# nodo_AS.net
KiCad netlist of a schematic drawn in EAGLE
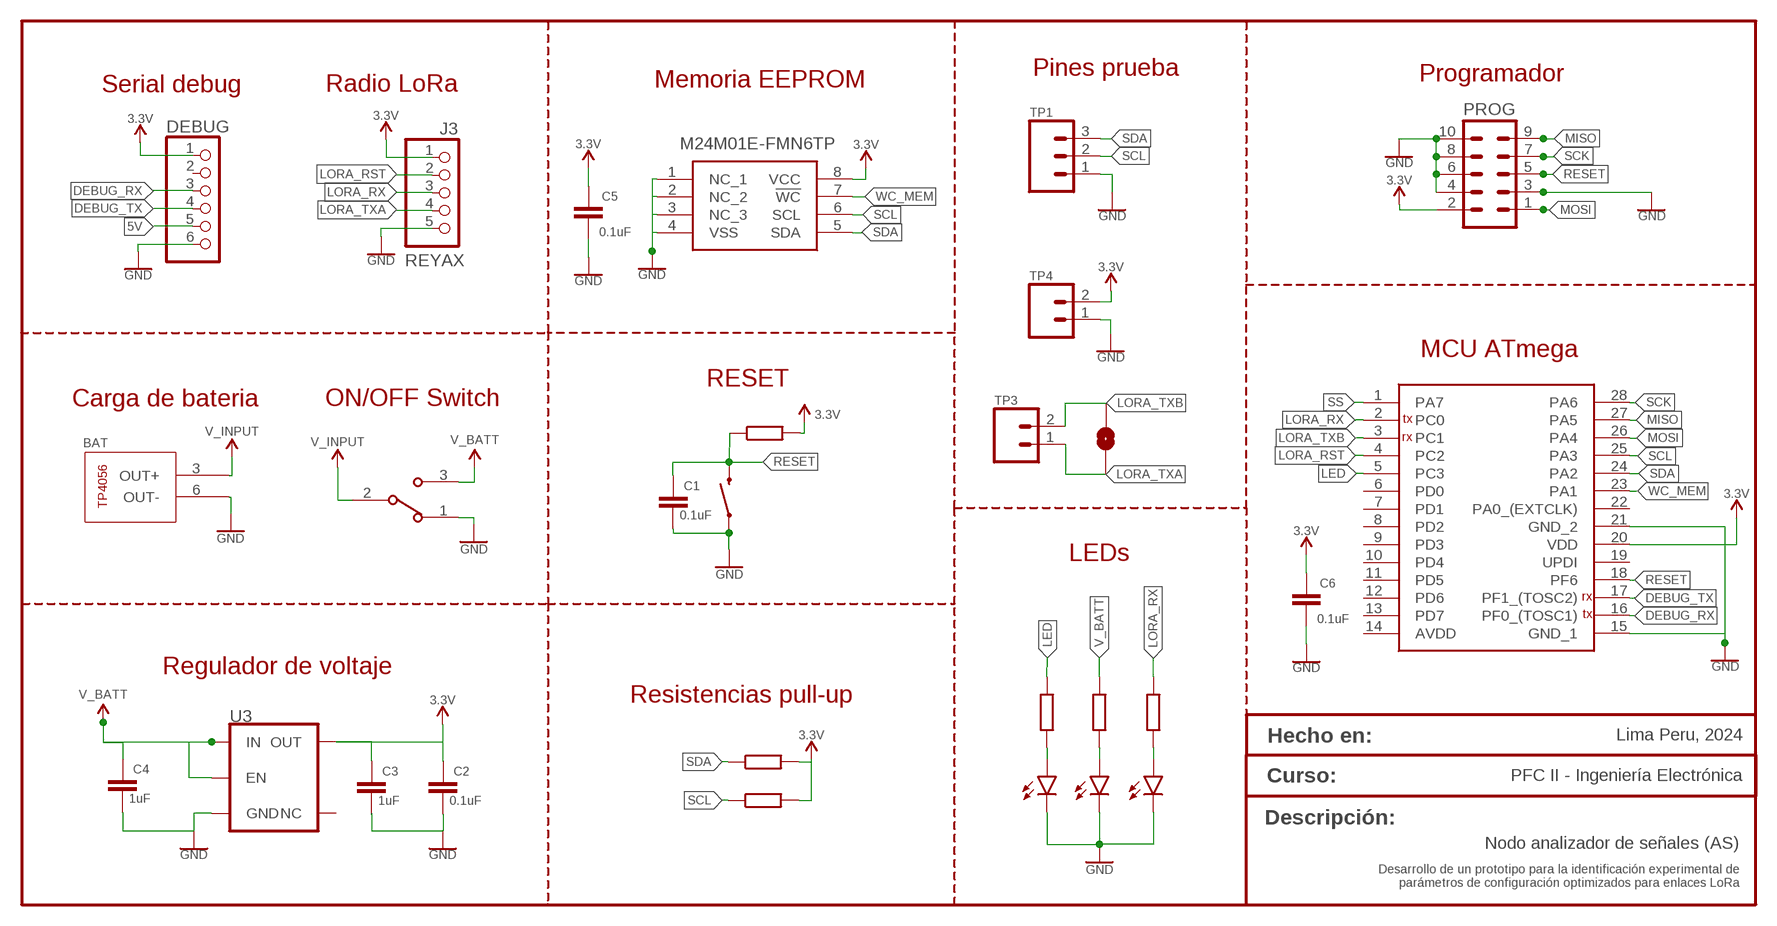
[diagram p0: schematic, sheet 1]

(export (version "E")
  (design (tool "Eeschema 10.0.6"))
  (components
    (comp (ref "BAT")
      (value "TP4056MODULE")
      (footprint "eagle-import:TP4056MODULE")
      (libsource (lib "eagle-import") (part "TP4056MODULE"))
    )
    (comp (ref "C1")
      (value "0.1uF")
      (footprint "eagle-import:C0603K")
      (libsource (lib "eagle-import") (part "C-EUC0603K"))
    )
    (comp (ref "C2")
      (value "0.1uF")
      (footprint "eagle-import:C0603K")
      (libsource (lib "eagle-import") (part "C-EUC0603K"))
    )
    (comp (ref "C3")
      (value "1uF")
      (footprint "eagle-import:C0603K")
      (libsource (lib "eagle-import") (part "C-EUC0603K"))
    )
    (comp (ref "C4")
      (value "1uF")
      (footprint "eagle-import:C0603K")
      (libsource (lib "eagle-import") (part "C-EUC0603K"))
    )
    (comp (ref "C5")
      (value "0.1uF")
      (footprint "eagle-import:0603")
      (libsource (lib "eagle-import") (part "0.1UF-0603-25V-(+80/-20%)"))
    )
    (comp (ref "C6")
      (value "0.1uF")
      (footprint "eagle-import:0603")
      (libsource (lib "eagle-import") (part "0.1UF-0603-25V-(+80/-20%)"))
    )
    (comp (ref "DEBUG")
      (value "PINHD-1X6")
      (footprint "eagle-import:1X06")
      (libsource (lib "eagle-import") (part "PINHD-1X6"))
    )
    (comp (ref "IC1")
      (value "ATMEGA3208-XU")
      (footprint "eagle-import:SOP65P780X200-28N")
      (fields (field (name "MOUSER_PART_NUMBER") "556-ATMEGA3208-XU"))
      (libsource (lib "eagle-import") (part "ATMEGA3208-XU"))
    )
    (comp (ref "IC2")
      (value "M24M01E-FMN6TP")
      (footprint "eagle-import:SOIC127P600X175-8N")
      (fields (field (name "MOUSER_PART_NUMBER") "511-M24M01E-FMN6TP"))
      (libsource (lib "eagle-import") (part "M24M01E-FMN6TP"))
    )
    (comp (ref "J3")
      (value "REYAX")
      (footprint "eagle-import:1X05")
      (libsource (lib "eagle-import") (part "PINHD-1X5"))
    )
    (comp (ref "JP1")
      (value "JUMPER-SMT_2_NO_NO-SILK_ROUND")
      (footprint "eagle-import:SMT-JUMPER_2_NO_NO-SILK_ROUND")
      (libsource (lib "eagle-import") (part "JUMPER-SMT_2_NO_NO-SILK_ROUND"))
    )
    (comp (ref "L_ON")
      (value "LED_3MM")
      (footprint "eagle-import:LEDRD254W50D405H1055")
      (libsource (lib "eagle-import") (part "LED_3MM"))
    )
    (comp (ref "L_ON1")
      (value "LED_3MM")
      (footprint "eagle-import:LEDRD254W50D405H1055")
      (libsource (lib "eagle-import") (part "LED_3MM"))
    )
    (comp (ref "L_ON2")
      (value "LED_3MM")
      (footprint "eagle-import:LEDRD254W50D405H1055")
      (libsource (lib "eagle-import") (part "LED_3MM"))
    )
    (comp (ref "PROG")
      (value "ML10-3M")
      (footprint "eagle-import:3M_10")
      (libsource (lib "eagle-import") (part "ML10-3M"))
    )
    (comp (ref "P_RESET")
      (value "MOMENTARY-SWITCH-SPST-PTH-6.0MM")
      (footprint "eagle-import:TACTILE_SWITCH_PTH_6.0MM")
      (libsource (lib "eagle-import") (part "MOMENTARY-SWITCH-SPST-PTH-6.0MM"))
    )
    (comp (ref "R1")
      (value "68")
      (footprint "eagle-import:0207_10")
      (libsource (lib "eagle-import") (part "R-EU_0207/10"))
    )
    (comp (ref "R2")
      (value "68")
      (footprint "eagle-import:0207_10")
      (libsource (lib "eagle-import") (part "R-EU_0207/10"))
    )
    (comp (ref "R3")
      (value "68")
      (footprint "eagle-import:0207_10")
      (libsource (lib "eagle-import") (part "R-EU_0207/10"))
    )
    (comp (ref "R4")
      (value "10k")
      (footprint "eagle-import:0207_10")
      (libsource (lib "eagle-import") (part "R-EU_0207/10"))
    )
    (comp (ref "R6")
      (value "1k")
      (footprint "eagle-import:0207_10")
      (libsource (lib "eagle-import") (part "R-EU_0207/10"))
    )
    (comp (ref "R7")
      (value "1k")
      (footprint "eagle-import:0207_10")
      (libsource (lib "eagle-import") (part "R-EU_0207/10"))
    )
    (comp (ref "SW1")
      (value "EG1213")
      (footprint "eagle-import:SW_EG1213")
      (fields (field (name "MF") "E-Switch"))
      (libsource (lib "eagle-import") (part "EG1213"))
    )
    (comp (ref "TP1")
      (value "CONN_03")
      (footprint "eagle-import:1X03")
      (libsource (lib "eagle-import") (part "CONN_03"))
    )
    (comp (ref "TP3")
      (value "CONN_02")
      (footprint "eagle-import:1X02")
      (libsource (lib "eagle-import") (part "CONN_02"))
    )
    (comp (ref "TP4")
      (value "CONN_02")
      (footprint "eagle-import:1X02")
      (libsource (lib "eagle-import") (part "CONN_02"))
    )
    (comp (ref "U3")
      (value "3.3V")
      (footprint "eagle-import:SOT23-5")
      (libsource (lib "eagle-import") (part "V_REG_AP2112K-3.3V"))
    )
  )
  (nets
    (net (code "1") (name "3.3V") (class "Default")
      (node (ref "C2") (pin "1") (pinfunction "1_1") (pintype "passive"))
      (node (ref "C3") (pin "1") (pinfunction "1_1") (pintype "passive"))
      (node (ref "C5") (pin "1") (pinfunction "1_1") (pintype "passive"))
      (node (ref "C6") (pin "1") (pinfunction "1_1") (pintype "passive"))
      (node (ref "DEBUG") (pin "1") (pinfunction "1_1") (pintype "passive"))
      (node (ref "IC1") (pin "20") (pinfunction "VDD_20") (pintype "bidirectional"))
      (node (ref "IC2") (pin "8") (pinfunction "VCC_8") (pintype "bidirectional"))
      (node (ref "J3") (pin "1") (pinfunction "1_1") (pintype "passive"))
      (node (ref "PROG") (pin "2") (pinfunction "2_2") (pintype "passive"))
      (node (ref "R4") (pin "2") (pinfunction "2_2") (pintype "passive"))
      (node (ref "R6") (pin "2") (pinfunction "2_2") (pintype "passive"))
      (node (ref "R7") (pin "2") (pinfunction "2_2") (pintype "passive"))
      (node (ref "TP4") (pin "2") (pinfunction "2_2") (pintype "passive"))
      (node (ref "U3") (pin "5") (pinfunction "OUT_5") (pintype "passive"))
    )
    (net (code "2") (name "5V") (class "Default")
      (node (ref "DEBUG") (pin "5") (pinfunction "5_5") (pintype "passive"))
    )
    (net (code "3") (name "DEBUG_RX") (class "Default")
      (node (ref "DEBUG") (pin "3") (pinfunction "3_3") (pintype "passive"))
      (node (ref "IC1") (pin "16") (pinfunction "PF0_(TOSC1)_16") (pintype "bidirectional"))
    )
    (net (code "4") (name "DEBUG_TX") (class "Default")
      (node (ref "DEBUG") (pin "4") (pinfunction "4_4") (pintype "passive"))
      (node (ref "IC1") (pin "17") (pinfunction "PF1_(TOSC2)_17") (pintype "bidirectional"))
    )
    (net (code "5") (name "GND") (class "Default")
      (node (ref "BAT") (pin "6") (pinfunction "OUT-_6") (pintype "passive"))
      (node (ref "C1") (pin "2") (pinfunction "2_2") (pintype "passive"))
      (node (ref "C2") (pin "2") (pinfunction "2_2") (pintype "passive"))
      (node (ref "C3") (pin "2") (pinfunction "2_2") (pintype "passive"))
      (node (ref "C4") (pin "2") (pinfunction "2_2") (pintype "passive"))
      (node (ref "C5") (pin "2") (pinfunction "2_2") (pintype "passive"))
      (node (ref "C6") (pin "2") (pinfunction "2_2") (pintype "passive"))
      (node (ref "DEBUG") (pin "6") (pinfunction "6_6") (pintype "passive"))
      (node (ref "IC1") (pin "15") (pinfunction "GND_1_15") (pintype "bidirectional"))
      (node (ref "IC1") (pin "21") (pinfunction "GND_2_21") (pintype "bidirectional"))
      (node (ref "IC2") (pin "1") (pinfunction "NC_1_1") (pintype "bidirectional"))
      (node (ref "IC2") (pin "2") (pinfunction "NC_2_2") (pintype "bidirectional"))
      (node (ref "IC2") (pin "3") (pinfunction "NC_3_3") (pintype "bidirectional"))
      (node (ref "IC2") (pin "4") (pinfunction "VSS_4") (pintype "bidirectional"))
      (node (ref "J3") (pin "5") (pinfunction "5_5") (pintype "passive"))
      (node (ref "L_ON") (pin "C") (pinfunction "C_C") (pintype "passive"))
      (node (ref "L_ON1") (pin "C") (pinfunction "C_C") (pintype "passive"))
      (node (ref "L_ON2") (pin "C") (pinfunction "C_C") (pintype "passive"))
      (node (ref "PROG") (pin "10") (pinfunction "10_10") (pintype "passive"))
      (node (ref "PROG") (pin "3") (pinfunction "3_3") (pintype "passive"))
      (node (ref "PROG") (pin "4") (pinfunction "4_4") (pintype "passive"))
      (node (ref "PROG") (pin "6") (pinfunction "6_6") (pintype "passive"))
      (node (ref "PROG") (pin "8") (pinfunction "8_8") (pintype "passive"))
      (node (ref "P_RESET") (pin "1") (pinfunction "1_1") (pintype "passive"))
      (node (ref "SW1") (pin "1") (pinfunction "1_1") (pintype "passive"))
      (node (ref "TP1") (pin "1") (pinfunction "1_1") (pintype "passive"))
      (node (ref "TP4") (pin "1") (pinfunction "1_1") (pintype "passive"))
      (node (ref "U3") (pin "2") (pinfunction "GND_2") (pintype "input"))
    )
    (net (code "6") (name "LED") (class "Default")
      (node (ref "IC1") (pin "5") (pinfunction "PC3_5") (pintype "bidirectional"))
      (node (ref "R3") (pin "1") (pinfunction "1_1") (pintype "passive"))
    )
    (net (code "7") (name "LORA_RST") (class "Default")
      (node (ref "IC1") (pin "4") (pinfunction "PC2_4") (pintype "bidirectional"))
      (node (ref "J3") (pin "2") (pinfunction "2_2") (pintype "passive"))
    )
    (net (code "8") (name "LORA_RX") (class "Default")
      (node (ref "IC1") (pin "2") (pinfunction "PC0_2") (pintype "bidirectional"))
      (node (ref "J3") (pin "3") (pinfunction "3_3") (pintype "passive"))
      (node (ref "R1") (pin "1") (pinfunction "1_1") (pintype "passive"))
    )
    (net (code "9") (name "LORA_TXA") (class "Default")
      (node (ref "J3") (pin "4") (pinfunction "4_4") (pintype "passive"))
      (node (ref "JP1") (pin "2") (pinfunction "2_2") (pintype "passive"))
      (node (ref "TP3") (pin "1") (pinfunction "1_1") (pintype "passive"))
    )
    (net (code "10") (name "LORA_TXB") (class "Default")
      (node (ref "IC1") (pin "3") (pinfunction "PC1_3") (pintype "bidirectional"))
      (node (ref "JP1") (pin "1") (pinfunction "1_1") (pintype "passive"))
      (node (ref "TP3") (pin "2") (pinfunction "2_2") (pintype "passive"))
    )
    (net (code "11") (name "MISO") (class "Default")
      (node (ref "IC1") (pin "27") (pinfunction "PA5_27") (pintype "bidirectional"))
      (node (ref "PROG") (pin "9") (pinfunction "9_9") (pintype "passive"))
    )
    (net (code "12") (name "MOSI") (class "Default")
      (node (ref "IC1") (pin "26") (pinfunction "PA4_26") (pintype "bidirectional"))
      (node (ref "PROG") (pin "1") (pinfunction "1_1") (pintype "passive"))
    )
    (net (code "13") (name "Net-(L_ON-PadA)") (class "Default")
      (node (ref "L_ON") (pin "A") (pinfunction "A_A") (pintype "passive"))
      (node (ref "R3") (pin "2") (pinfunction "2_2") (pintype "passive"))
    )
    (net (code "14") (name "Net-(L_ON1-PadA)") (class "Default")
      (node (ref "L_ON1") (pin "A") (pinfunction "A_A") (pintype "passive"))
      (node (ref "R2") (pin "2") (pinfunction "2_2") (pintype "passive"))
    )
    (net (code "15") (name "Net-(L_ON2-PadA)") (class "Default")
      (node (ref "L_ON2") (pin "A") (pinfunction "A_A") (pintype "passive"))
      (node (ref "R1") (pin "2") (pinfunction "2_2") (pintype "passive"))
    )
    (net (code "16") (name "RESET") (class "Default")
      (node (ref "C1") (pin "1") (pinfunction "1_1") (pintype "passive"))
      (node (ref "IC1") (pin "18") (pinfunction "PF6_18") (pintype "bidirectional"))
      (node (ref "PROG") (pin "5") (pinfunction "5_5") (pintype "passive"))
      (node (ref "P_RESET") (pin "3") (pinfunction "2_3") (pintype "passive"))
      (node (ref "R4") (pin "1") (pinfunction "1_1") (pintype "passive"))
    )
    (net (code "17") (name "SCK") (class "Default")
      (node (ref "IC1") (pin "28") (pinfunction "PA6_28") (pintype "bidirectional"))
      (node (ref "PROG") (pin "7") (pinfunction "7_7") (pintype "passive"))
    )
    (net (code "18") (name "SCL") (class "Default")
      (node (ref "IC1") (pin "25") (pinfunction "PA3_25") (pintype "bidirectional"))
      (node (ref "IC2") (pin "6") (pinfunction "SCL_6") (pintype "bidirectional"))
      (node (ref "R7") (pin "1") (pinfunction "1_1") (pintype "passive"))
      (node (ref "TP1") (pin "2") (pinfunction "2_2") (pintype "passive"))
    )
    (net (code "19") (name "SDA") (class "Default")
      (node (ref "IC1") (pin "24") (pinfunction "PA2_24") (pintype "bidirectional"))
      (node (ref "IC2") (pin "5") (pinfunction "SDA_5") (pintype "bidirectional"))
      (node (ref "R6") (pin "1") (pinfunction "1_1") (pintype "passive"))
      (node (ref "TP1") (pin "3") (pinfunction "3_3") (pintype "passive"))
    )
    (net (code "20") (name "SS") (class "Default")
      (node (ref "IC1") (pin "1") (pinfunction "PA7_1") (pintype "bidirectional"))
    )
    (net (code "21") (name "V_BATT") (class "Default")
      (node (ref "C4") (pin "1") (pinfunction "1_1") (pintype "passive"))
      (node (ref "R2") (pin "1") (pinfunction "1_1") (pintype "passive"))
      (node (ref "SW1") (pin "3") (pinfunction "3_3") (pintype "passive"))
      (node (ref "U3") (pin "1") (pinfunction "IN_1") (pintype "input"))
      (node (ref "U3") (pin "3") (pinfunction "EN_3") (pintype "input"))
    )
    (net (code "22") (name "V_INPUT") (class "Default")
      (node (ref "BAT") (pin "3") (pinfunction "OUT+_3") (pintype "passive"))
      (node (ref "SW1") (pin "2") (pinfunction "2_2") (pintype "passive"))
    )
    (net (code "23") (name "WC_MEM") (class "Default")
      (node (ref "IC1") (pin "23") (pinfunction "PA1_23") (pintype "bidirectional"))
      (node (ref "IC2") (pin "7") (pinfunction "~{WC}_7") (pintype "bidirectional"))
    )
    (net (code "24") (name "unconnected-(DEBUG-Pad2)") (class "Default")
      (node (ref "DEBUG") (pin "2") (pinfunction "2_2") (pintype "passive"))
    )
    (net (code "25") (name "unconnected-(IC1-AVDD-Pad14)") (class "Default")
      (node (ref "IC1") (pin "14") (pinfunction "AVDD_14") (pintype "bidirectional"))
    )
    (net (code "26") (name "unconnected-(IC1-PA0_(EXTCLK)-Pad22)") (class "Default")
      (node (ref "IC1") (pin "22") (pinfunction "PA0_(EXTCLK)_22") (pintype "bidirectional"))
    )
    (net (code "27") (name "unconnected-(IC1-PD0-Pad6)") (class "Default")
      (node (ref "IC1") (pin "6") (pinfunction "PD0_6") (pintype "bidirectional"))
    )
    (net (code "28") (name "unconnected-(IC1-PD1-Pad7)") (class "Default")
      (node (ref "IC1") (pin "7") (pinfunction "PD1_7") (pintype "bidirectional"))
    )
    (net (code "29") (name "unconnected-(IC1-PD2-Pad8)") (class "Default")
      (node (ref "IC1") (pin "8") (pinfunction "PD2_8") (pintype "bidirectional"))
    )
    (net (code "30") (name "unconnected-(IC1-PD3-Pad9)") (class "Default")
      (node (ref "IC1") (pin "9") (pinfunction "PD3_9") (pintype "bidirectional"))
    )
    (net (code "31") (name "unconnected-(IC1-PD4-Pad10)") (class "Default")
      (node (ref "IC1") (pin "10") (pinfunction "PD4_10") (pintype "bidirectional"))
    )
    (net (code "32") (name "unconnected-(IC1-PD5-Pad11)") (class "Default")
      (node (ref "IC1") (pin "11") (pinfunction "PD5_11") (pintype "bidirectional"))
    )
    (net (code "33") (name "unconnected-(IC1-PD6-Pad12)") (class "Default")
      (node (ref "IC1") (pin "12") (pinfunction "PD6_12") (pintype "bidirectional"))
    )
    (net (code "34") (name "unconnected-(IC1-PD7-Pad13)") (class "Default")
      (node (ref "IC1") (pin "13") (pinfunction "PD7_13") (pintype "bidirectional"))
    )
    (net (code "35") (name "unconnected-(IC1-UPDI-Pad19)") (class "Default")
      (node (ref "IC1") (pin "19") (pinfunction "UPDI_19") (pintype "bidirectional"))
    )
    (net (code "36") (name "unconnected-(U3-NC-Pad4)") (class "Default")
      (node (ref "U3") (pin "4") (pinfunction "NC_4") (pintype "no_connect"))
    )
  )
)
